# IsolatorTop.net
KiCad netlist of a schematic drawn in Altium Designer
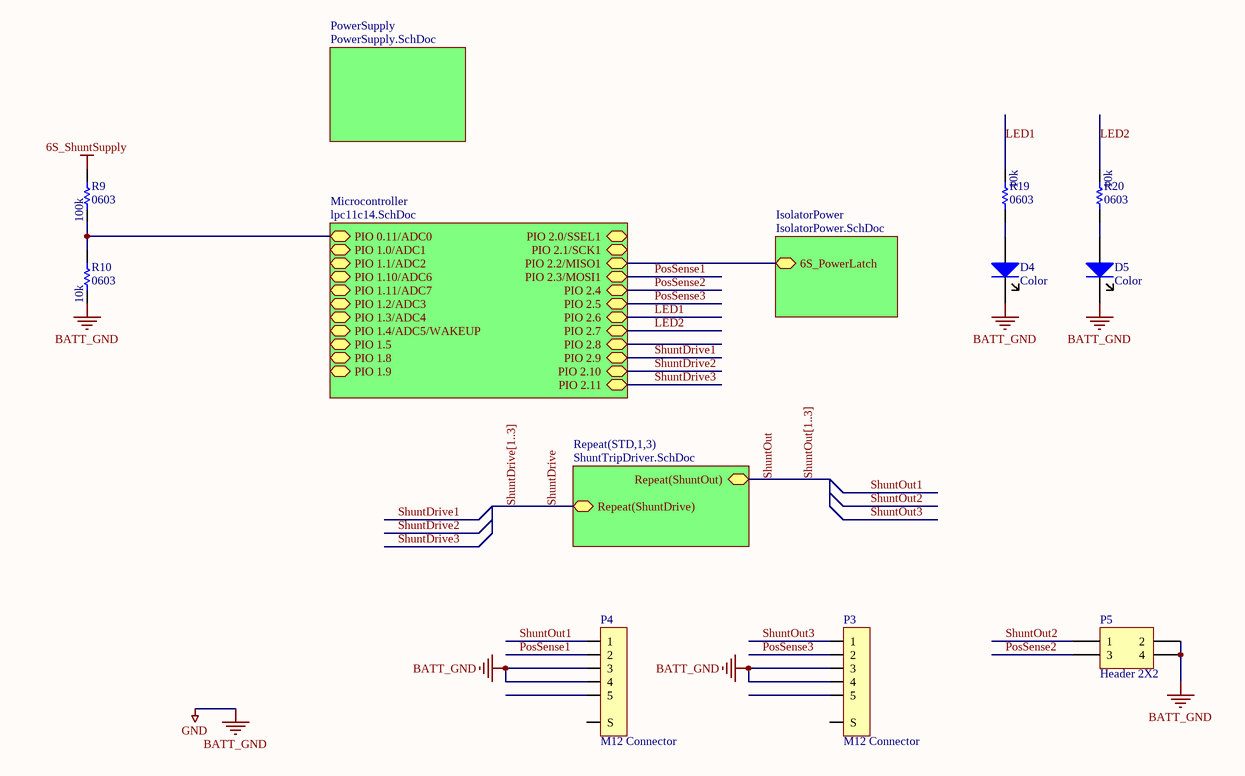
[diagram p0: IsolatorTop.SchDoc]

(export (version "E")
  (design (tool "Eeschema 10.0.6"))
  (components
    (comp (ref "D4")
      (value "Color")
      (footprint "CAP_0.1_POL")
      (fields (field (name "Comment") "LED"))
      (libsource (lib "UNSW_LIB") (part "D LED"))
    )
    (comp (ref "D5")
      (value "Color")
      (footprint "CAP_0.1_POL")
      (fields (field (name "Comment") "LED"))
      (libsource (lib "UNSW_LIB") (part "D LED"))
    )
    (comp (ref "P3")
      (value "M12 Connector")
      (footprint "M12_5P_VERT")
      (description "5 Pin")
      (libsource (lib "UNSW_LIB") (part "M12 Connector"))
    )
    (comp (ref "P4")
      (value "M12 Connector")
      (footprint "M12_5P_VERT")
      (description "5 Pin")
      (libsource (lib "UNSW_LIB") (part "M12 Connector"))
    )
    (comp (ref "P5")
      (value "Header 2X2")
      (footprint "HDR2X2")
      (description "Header, 2-Pin, Dual row")
      (fields (field (name "PUBLISHER") "Altium Limited"))
      (libsource (lib "Miscellaneous Connectors") (part "Header 2X2"))
    )
    (comp (ref "R9")
      (value "100k")
      (footprint "0603_M")
      (description "Resistor")
      (fields (field (name "PACKAGE") "0603") (field (name "Comment") "R"))
      (libsource (lib "UNSW_LIB") (part "R"))
    )
    (comp (ref "R10")
      (value "10k")
      (footprint "0603_M")
      (description "Resistor")
      (fields (field (name "PACKAGE") "0603") (field (name "Comment") "R"))
      (libsource (lib "UNSW_LIB") (part "R"))
    )
    (comp (ref "R19")
      (value "10k")
      (footprint "0603_M")
      (description "Resistor")
      (fields (field (name "PACKAGE") "0603") (field (name "Comment") "R"))
      (libsource (lib "UNSW_LIB") (part "R"))
    )
    (comp (ref "R20")
      (value "10k")
      (footprint "0603_M")
      (description "Resistor")
      (fields (field (name "PACKAGE") "0603") (field (name "Comment") "R"))
      (libsource (lib "UNSW_LIB") (part "R"))
    )
  )
  (nets
    (net (code "2") (name "/LED1") (class "Default")
      (node (ref "R19") (pin "2") (pinfunction "2_2") (pintype "passive"))
    )
    (net (code "3") (name "/LED2") (class "Default")
      (node (ref "R20") (pin "2") (pinfunction "2_2") (pintype "passive"))
    )
    (net (code "4") (name "/PIO 0.11{slash}ADC0") (class "Default")
      (node (ref "R10") (pin "1") (pinfunction "1_1") (pintype "passive"))
      (node (ref "R9") (pin "2") (pinfunction "2_2") (pintype "passive"))
    )
    (net (code "18") (name "/PosSense1") (class "Default")
      (node (ref "P4") (pin "2") (pinfunction "2_2") (pintype "passive"))
    )
    (net (code "19") (name "/PosSense2") (class "Default")
      (node (ref "P5") (pin "3") (pinfunction "3_3") (pintype "passive"))
    )
    (net (code "20") (name "/PosSense3") (class "Default")
      (node (ref "P3") (pin "2") (pinfunction "2_2") (pintype "passive"))
    )
    (net (code "27") (name "/ShuntOut1") (class "Default")
      (node (ref "P4") (pin "1") (pinfunction "1_1") (pintype "passive"))
    )
    (net (code "28") (name "/ShuntOut2") (class "Default")
      (node (ref "P5") (pin "1") (pinfunction "1_1") (pintype "passive"))
    )
    (net (code "29") (name "/ShuntOut3") (class "Default")
      (node (ref "P3") (pin "1") (pinfunction "1_1") (pintype "passive"))
    )
    (net (code "31") (name "6S_ShuntSupply") (class "Default")
      (node (ref "R9") (pin "1") (pinfunction "1_1") (pintype "passive"))
    )
    (net (code "32") (name "BATT_GND") (class "Default")
      (node (ref "D4") (pin "2") (pinfunction "K_2") (pintype "passive"))
      (node (ref "D5") (pin "2") (pinfunction "K_2") (pintype "passive"))
      (node (ref "P3") (pin "3") (pinfunction "3_3") (pintype "passive"))
      (node (ref "P3") (pin "4") (pinfunction "4_4") (pintype "passive"))
      (node (ref "P4") (pin "3") (pinfunction "3_3") (pintype "passive"))
      (node (ref "P4") (pin "4") (pinfunction "4_4") (pintype "passive"))
      (node (ref "P5") (pin "2") (pinfunction "2_2") (pintype "passive"))
      (node (ref "P5") (pin "4") (pinfunction "4_4") (pintype "passive"))
      (node (ref "R10") (pin "2") (pinfunction "2_2") (pintype "passive"))
    )
    (net (code "33") (name "Net-(D4-A)") (class "Default")
      (node (ref "D4") (pin "1") (pinfunction "A_1") (pintype "passive"))
      (node (ref "R19") (pin "1") (pinfunction "1_1") (pintype "passive"))
    )
    (net (code "34") (name "Net-(D5-A)") (class "Default")
      (node (ref "D5") (pin "1") (pinfunction "A_1") (pintype "passive"))
      (node (ref "R20") (pin "1") (pinfunction "1_1") (pintype "passive"))
    )
    (net (code "35") (name "unconnected-(P3-Pad5)") (class "Default")
      (node (ref "P3") (pin "5") (pinfunction "5_5") (pintype "passive"))
    )
    (net (code "36") (name "unconnected-(P3-PadS)") (class "Default")
      (node (ref "P3") (pin "S") (pinfunction "S_S") (pintype "passive"))
    )
    (net (code "37") (name "unconnected-(P4-Pad5)") (class "Default")
      (node (ref "P4") (pin "5") (pinfunction "5_5") (pintype "passive"))
    )
    (net (code "38") (name "unconnected-(P4-PadS)") (class "Default")
      (node (ref "P4") (pin "S") (pinfunction "S_S") (pintype "passive"))
    )
  )
)
